# Driver.net
KiCad netlist of a schematic drawn in EAGLE
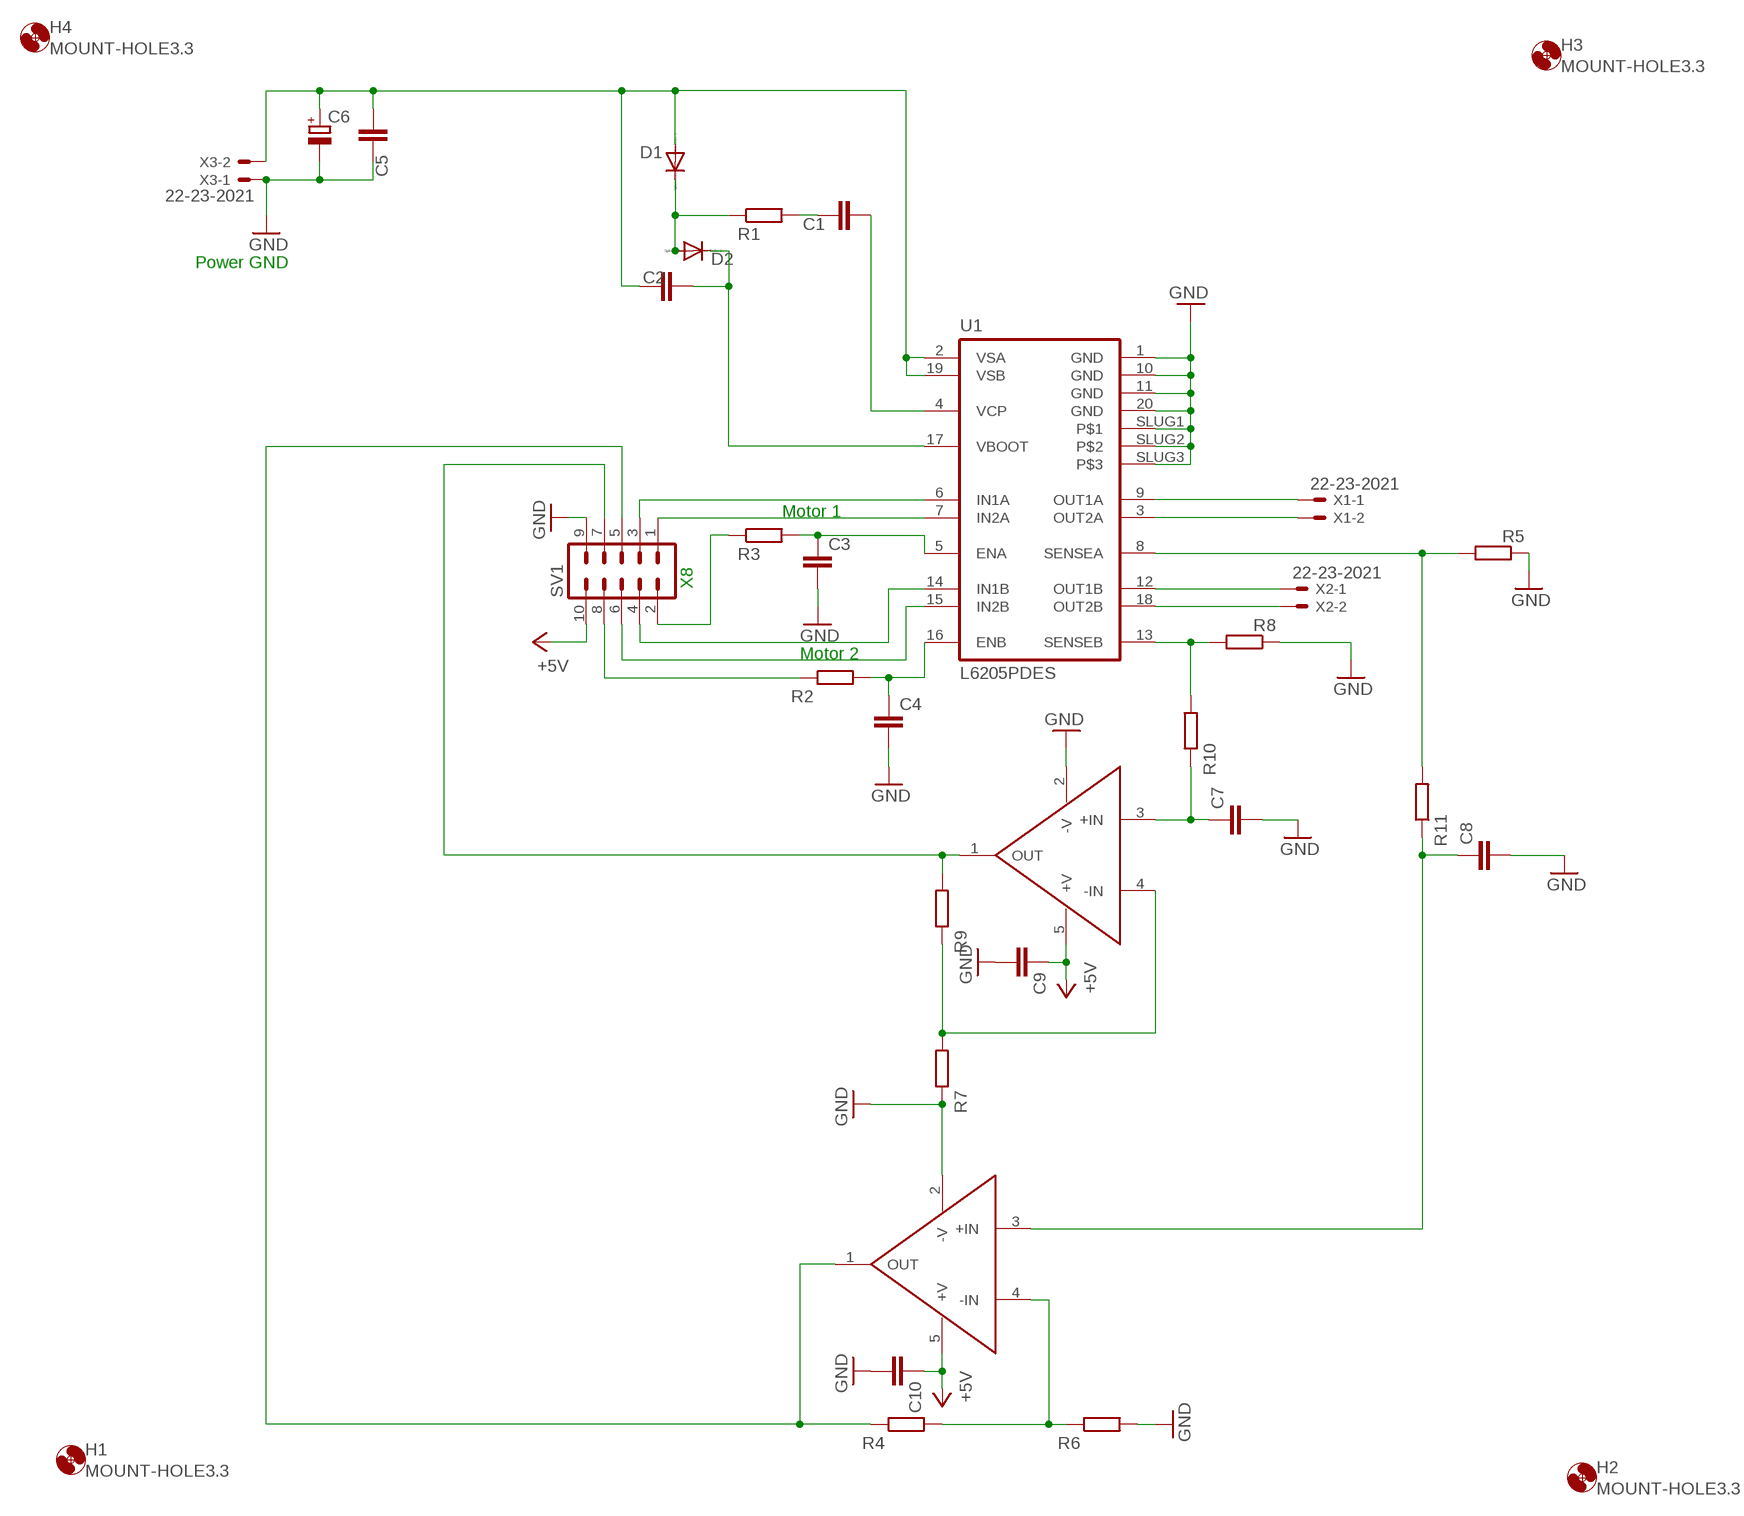
[diagram p0: schematic, sheet 1]

(export (version "E")
  (design (tool "Eeschema 10.0.6"))
  (components
    (comp (ref "C1")
      (value "C-EUC0805K")
      (footprint "eagle-import:C0805K")
      (libsource (lib "eagle-import") (part "C-EUC0805K"))
    )
    (comp (ref "C2")
      (value "C-EUC0805K")
      (footprint "eagle-import:C0805K")
      (libsource (lib "eagle-import") (part "C-EUC0805K"))
    )
    (comp (ref "C3")
      (value "C-EUC0805")
      (footprint "eagle-import:C0805")
      (libsource (lib "eagle-import") (part "C-EUC0805"))
    )
    (comp (ref "C4")
      (value "C-EUC0805")
      (footprint "eagle-import:C0805")
      (libsource (lib "eagle-import") (part "C-EUC0805"))
    )
    (comp (ref "C5")
      (value "C-EUC0805K")
      (footprint "eagle-import:C0805K")
      (libsource (lib "eagle-import") (part "C-EUC0805K"))
    )
    (comp (ref "C6")
      (value "CPOL-EUE")
      (footprint "eagle-import:PANASONIC_E")
      (libsource (lib "eagle-import") (part "CPOL-EUE"))
    )
    (comp (ref "C7")
      (value "C-EUC0805")
      (footprint "eagle-import:C0805")
      (libsource (lib "eagle-import") (part "C-EUC0805"))
    )
    (comp (ref "C8")
      (value "C-EUC0805")
      (footprint "eagle-import:C0805")
      (libsource (lib "eagle-import") (part "C-EUC0805"))
    )
    (comp (ref "C9")
      (value "C-EUC0805")
      (footprint "eagle-import:C0805")
      (libsource (lib "eagle-import") (part "C-EUC0805"))
    )
    (comp (ref "C10")
      (value "C-EUC0805")
      (footprint "eagle-import:C0805")
      (libsource (lib "eagle-import") (part "C-EUC0805"))
    )
    (comp (ref "D1")
      (value "DIODE-MINIMELF")
      (footprint "eagle-import:MINIMELF")
      (libsource (lib "eagle-import") (part "DIODE-MINIMELF"))
    )
    (comp (ref "D2")
      (value "DIODE-MINIMELF")
      (footprint "eagle-import:MINIMELF")
      (libsource (lib "eagle-import") (part "DIODE-MINIMELF"))
    )
    (comp (ref "H1")
      (value "MOUNT-HOLE3.3")
      (footprint "eagle-import:3,3")
      (libsource (lib "eagle-import") (part "MOUNT-HOLE3.3"))
    )
    (comp (ref "H2")
      (value "MOUNT-HOLE3.3")
      (footprint "eagle-import:3,3")
      (libsource (lib "eagle-import") (part "MOUNT-HOLE3.3"))
    )
    (comp (ref "H3")
      (value "MOUNT-HOLE3.3")
      (footprint "eagle-import:3,3")
      (libsource (lib "eagle-import") (part "MOUNT-HOLE3.3"))
    )
    (comp (ref "H4")
      (value "MOUNT-HOLE3.3")
      (footprint "eagle-import:3,3")
      (libsource (lib "eagle-import") (part "MOUNT-HOLE3.3"))
    )
    (comp (ref "R1")
      (value "R-EU_MELF0204W")
      (footprint "eagle-import:MINI_MELF-0204W")
      (libsource (lib "eagle-import") (part "R-EU_MELF0204W"))
    )
    (comp (ref "R2")
      (value "R-EU_MELF0204W")
      (footprint "eagle-import:MINI_MELF-0204W")
      (libsource (lib "eagle-import") (part "R-EU_MELF0204W"))
    )
    (comp (ref "R3")
      (value "R-EU_MELF0204W")
      (footprint "eagle-import:MINI_MELF-0204W")
      (libsource (lib "eagle-import") (part "R-EU_MELF0204W"))
    )
    (comp (ref "R4")
      (value "R-EU_MELF0204W")
      (footprint "eagle-import:MINI_MELF-0204W")
      (libsource (lib "eagle-import") (part "R-EU_MELF0204W"))
    )
    (comp (ref "R5")
      (value "R-EU_R2512W")
      (footprint "eagle-import:R2512W")
      (libsource (lib "eagle-import") (part "R-EU_R2512W"))
    )
    (comp (ref "R6")
      (value "R-EU_MELF0204W")
      (footprint "eagle-import:MINI_MELF-0204W")
      (libsource (lib "eagle-import") (part "R-EU_MELF0204W"))
    )
    (comp (ref "R7")
      (value "R-EU_MELF0204W")
      (footprint "eagle-import:MINI_MELF-0204W")
      (libsource (lib "eagle-import") (part "R-EU_MELF0204W"))
    )
    (comp (ref "R8")
      (value "R-EU_R2512W")
      (footprint "eagle-import:R2512W")
      (libsource (lib "eagle-import") (part "R-EU_R2512W"))
    )
    (comp (ref "R9")
      (value "R-EU_MELF0204W")
      (footprint "eagle-import:MINI_MELF-0204W")
      (libsource (lib "eagle-import") (part "R-EU_MELF0204W"))
    )
    (comp (ref "R10")
      (value "R-EU_MELF0204W")
      (footprint "eagle-import:MINI_MELF-0204W")
      (libsource (lib "eagle-import") (part "R-EU_MELF0204W"))
    )
    (comp (ref "R11")
      (value "R-EU_MELF0204W")
      (footprint "eagle-import:MINI_MELF-0204W")
      (libsource (lib "eagle-import") (part "R-EU_MELF0204W"))
    )
    (comp (ref "SV1")
      (value "ML10")
      (footprint "eagle-import:ML10")
      (libsource (lib "eagle-import") (part "ML10"))
    )
    (comp (ref "U$2")
      (value "LM7301")
      (footprint "eagle-import:SOT23-5")
      (libsource (lib "eagle-import") (part "LM7301"))
    )
    (comp (ref "U$3")
      (value "LM7301")
      (footprint "eagle-import:SOT23-5")
      (libsource (lib "eagle-import") (part "LM7301"))
    )
    (comp (ref "U1")
      (value "L6205PDES")
      (footprint "eagle-import:SO20POWER2")
      (libsource (lib "eagle-import") (part "L6205PDES"))
    )
    (comp (ref "X1")
      (value "22-23-2021")
      (footprint "eagle-import:22-23-2021")
      (fields (field (name "MF") "MOLEX"))
      (libsource (lib "eagle-import") (part "22-23-2021"))
    )
    (comp (ref "X2")
      (value "22-23-2021")
      (footprint "eagle-import:22-23-2021")
      (fields (field (name "MF") "MOLEX"))
      (libsource (lib "eagle-import") (part "22-23-2021"))
    )
    (comp (ref "X3")
      (value "22-23-2021")
      (footprint "eagle-import:22-23-2021")
      (fields (field (name "MF") "MOLEX"))
      (libsource (lib "eagle-import") (part "22-23-2021"))
    )
  )
  (nets
    (net (code "1") (name "+5V") (class "Default")
      (node (ref "C10") (pin "1") (pinfunction "1_1") (pintype "passive"))
      (node (ref "C9") (pin "1") (pinfunction "1_1") (pintype "passive"))
      (node (ref "SV1") (pin "10") (pinfunction "10_10") (pintype "passive"))
      (node (ref "U$2") (pin "5") (pinfunction "+V_5") (pintype "power_in"))
      (node (ref "U$3") (pin "5") (pinfunction "+V_5") (pintype "power_in"))
    )
    (net (code "2") (name "GND") (class "Default")
      (node (ref "C10") (pin "2") (pinfunction "2_2") (pintype "passive"))
      (node (ref "C3") (pin "2") (pinfunction "2_2") (pintype "passive"))
      (node (ref "C4") (pin "2") (pinfunction "2_2") (pintype "passive"))
      (node (ref "C5") (pin "1") (pinfunction "1_1") (pintype "passive"))
      (node (ref "C6") (pin "-") (pinfunction "-_-") (pintype "passive"))
      (node (ref "C7") (pin "2") (pinfunction "2_2") (pintype "passive"))
      (node (ref "C8") (pin "2") (pinfunction "2_2") (pintype "passive"))
      (node (ref "C9") (pin "2") (pinfunction "2_2") (pintype "passive"))
      (node (ref "R5") (pin "1") (pinfunction "1_1") (pintype "passive"))
      (node (ref "R6") (pin "2") (pinfunction "2_2") (pintype "passive"))
      (node (ref "R7") (pin "1") (pinfunction "1_1") (pintype "passive"))
      (node (ref "R8") (pin "1") (pinfunction "1_1") (pintype "passive"))
      (node (ref "SV1") (pin "9") (pinfunction "9_9") (pintype "passive"))
      (node (ref "U$2") (pin "2") (pinfunction "-V_2") (pintype "power_in"))
      (node (ref "U$3") (pin "2") (pinfunction "-V_2") (pintype "power_in"))
      (node (ref "U1") (pin "1") (pinfunction "GND_1") (pintype "power_in"))
      (node (ref "U1") (pin "10") (pinfunction "GND_10") (pintype "power_in"))
      (node (ref "U1") (pin "11") (pinfunction "GND_11") (pintype "power_in"))
      (node (ref "U1") (pin "20") (pinfunction "GND_20") (pintype "power_in"))
      (node (ref "U1") (pin "SLUG1") (pinfunction "P$1_SLUG1") (pintype "bidirectional"))
      (node (ref "U1") (pin "SLUG2") (pinfunction "P$2_SLUG2") (pintype "bidirectional"))
      (node (ref "U1") (pin "SLUG3") (pinfunction "P$3_SLUG3") (pintype "bidirectional"))
      (node (ref "X3") (pin "1") (pinfunction "S_1") (pintype "passive"))
    )
    (net (code "3") (name "Net-(C1-Pad1)") (class "Default")
      (node (ref "C1") (pin "1") (pinfunction "1_1") (pintype "passive"))
      (node (ref "R1") (pin "2") (pinfunction "2_2") (pintype "passive"))
    )
    (net (code "4") (name "Net-(D1-PadC)") (class "Default")
      (node (ref "D1") (pin "C") (pinfunction "C_C") (pintype "passive"))
      (node (ref "D2") (pin "A") (pinfunction "A_A") (pintype "passive"))
      (node (ref "R1") (pin "1") (pinfunction "1_1") (pintype "passive"))
    )
    (net (code "5") (name "Net-(R2-Pad1)") (class "Default")
      (node (ref "R2") (pin "1") (pinfunction "1_1") (pintype "passive"))
      (node (ref "SV1") (pin "8") (pinfunction "8_8") (pintype "passive"))
    )
    (net (code "6") (name "Net-(R3-Pad1)") (class "Default")
      (node (ref "R3") (pin "1") (pinfunction "1_1") (pintype "passive"))
      (node (ref "SV1") (pin "2") (pinfunction "2_2") (pintype "passive"))
    )
    (net (code "7") (name "Net-(U$2-+IN)") (class "Default")
      (node (ref "C8") (pin "1") (pinfunction "1_1") (pintype "passive"))
      (node (ref "R11") (pin "1") (pinfunction "1_1") (pintype "passive"))
      (node (ref "U$2") (pin "3") (pinfunction "+IN_3") (pintype "input"))
    )
    (net (code "8") (name "Net-(U$2--IN)") (class "Default")
      (node (ref "R4") (pin "2") (pinfunction "2_2") (pintype "passive"))
      (node (ref "R6") (pin "1") (pinfunction "1_1") (pintype "passive"))
      (node (ref "U$2") (pin "4") (pinfunction "-IN_4") (pintype "input"))
    )
    (net (code "9") (name "Net-(U$2-OUT)") (class "Default")
      (node (ref "R4") (pin "1") (pinfunction "1_1") (pintype "passive"))
      (node (ref "SV1") (pin "5") (pinfunction "5_5") (pintype "passive"))
      (node (ref "U$2") (pin "1") (pinfunction "OUT_1") (pintype "output"))
    )
    (net (code "10") (name "Net-(U$3-+IN)") (class "Default")
      (node (ref "C7") (pin "1") (pinfunction "1_1") (pintype "passive"))
      (node (ref "R10") (pin "1") (pinfunction "1_1") (pintype "passive"))
      (node (ref "U$3") (pin "3") (pinfunction "+IN_3") (pintype "input"))
    )
    (net (code "11") (name "Net-(U$3--IN)") (class "Default")
      (node (ref "R7") (pin "2") (pinfunction "2_2") (pintype "passive"))
      (node (ref "R9") (pin "1") (pinfunction "1_1") (pintype "passive"))
      (node (ref "U$3") (pin "4") (pinfunction "-IN_4") (pintype "input"))
    )
    (net (code "12") (name "Net-(U$3-OUT)") (class "Default")
      (node (ref "R9") (pin "2") (pinfunction "2_2") (pintype "passive"))
      (node (ref "SV1") (pin "7") (pinfunction "7_7") (pintype "passive"))
      (node (ref "U$3") (pin "1") (pinfunction "OUT_1") (pintype "output"))
    )
    (net (code "13") (name "Net-(U1-ENA)") (class "Default")
      (node (ref "C3") (pin "1") (pinfunction "1_1") (pintype "passive"))
      (node (ref "R3") (pin "2") (pinfunction "2_2") (pintype "passive"))
      (node (ref "U1") (pin "5") (pinfunction "ENA_5") (pintype "bidirectional"))
    )
    (net (code "14") (name "Net-(U1-ENB)") (class "Default")
      (node (ref "C4") (pin "1") (pinfunction "1_1") (pintype "passive"))
      (node (ref "R2") (pin "2") (pinfunction "2_2") (pintype "passive"))
      (node (ref "U1") (pin "16") (pinfunction "ENB_16") (pintype "bidirectional"))
    )
    (net (code "15") (name "Net-(U1-IN1A)") (class "Default")
      (node (ref "SV1") (pin "3") (pinfunction "3_3") (pintype "passive"))
      (node (ref "U1") (pin "6") (pinfunction "IN1A_6") (pintype "input"))
    )
    (net (code "16") (name "Net-(U1-IN1B)") (class "Default")
      (node (ref "SV1") (pin "4") (pinfunction "4_4") (pintype "passive"))
      (node (ref "U1") (pin "14") (pinfunction "IN1B_14") (pintype "input"))
    )
    (net (code "17") (name "Net-(U1-IN2A)") (class "Default")
      (node (ref "SV1") (pin "1") (pinfunction "1_1") (pintype "passive"))
      (node (ref "U1") (pin "7") (pinfunction "IN2A_7") (pintype "input"))
    )
    (net (code "18") (name "Net-(U1-IN2B)") (class "Default")
      (node (ref "SV1") (pin "6") (pinfunction "6_6") (pintype "passive"))
      (node (ref "U1") (pin "15") (pinfunction "IN2B_15") (pintype "input"))
    )
    (net (code "19") (name "Net-(U1-OUT1A)") (class "Default")
      (node (ref "U1") (pin "9") (pinfunction "OUT1A_9") (pintype "output"))
      (node (ref "X1") (pin "1") (pinfunction "S_1") (pintype "passive"))
    )
    (net (code "20") (name "Net-(U1-OUT1B)") (class "Default")
      (node (ref "U1") (pin "12") (pinfunction "OUT1B_12") (pintype "output"))
      (node (ref "X2") (pin "1") (pinfunction "S_1") (pintype "passive"))
    )
    (net (code "21") (name "Net-(U1-OUT2A)") (class "Default")
      (node (ref "U1") (pin "3") (pinfunction "OUT2A_3") (pintype "output"))
      (node (ref "X1") (pin "2") (pinfunction "S_2") (pintype "passive"))
    )
    (net (code "22") (name "Net-(U1-OUT2B)") (class "Default")
      (node (ref "U1") (pin "18") (pinfunction "OUT2B_18") (pintype "output"))
      (node (ref "X2") (pin "2") (pinfunction "S_2") (pintype "passive"))
    )
    (net (code "23") (name "Net-(U1-SENSEA)") (class "Default")
      (node (ref "R11") (pin "2") (pinfunction "2_2") (pintype "passive"))
      (node (ref "R5") (pin "2") (pinfunction "2_2") (pintype "passive"))
      (node (ref "U1") (pin "8") (pinfunction "SENSEA_8") (pintype "power_in"))
    )
    (net (code "24") (name "Net-(U1-SENSEB)") (class "Default")
      (node (ref "R10") (pin "2") (pinfunction "2_2") (pintype "passive"))
      (node (ref "R8") (pin "2") (pinfunction "2_2") (pintype "passive"))
      (node (ref "U1") (pin "13") (pinfunction "SENSEB_13") (pintype "power_in"))
    )
    (net (code "25") (name "Net-(U1-VBOOT)") (class "Default")
      (node (ref "C2") (pin "2") (pinfunction "2_2") (pintype "passive"))
      (node (ref "D2") (pin "C") (pinfunction "C_C") (pintype "passive"))
      (node (ref "U1") (pin "17") (pinfunction "VBOOT_17") (pintype "passive"))
    )
    (net (code "26") (name "Net-(U1-VCP)") (class "Default")
      (node (ref "C1") (pin "2") (pinfunction "2_2") (pintype "passive"))
      (node (ref "U1") (pin "4") (pinfunction "VCP_4") (pintype "passive"))
    )
    (net (code "27") (name "Net-(U1-VSA)") (class "Default")
      (node (ref "C2") (pin "1") (pinfunction "1_1") (pintype "passive"))
      (node (ref "C5") (pin "2") (pinfunction "2_2") (pintype "passive"))
      (node (ref "C6") (pin "+") (pinfunction "+_+") (pintype "passive"))
      (node (ref "D1") (pin "A") (pinfunction "A_A") (pintype "passive"))
      (node (ref "U1") (pin "19") (pinfunction "VSB_19") (pintype "power_in"))
      (node (ref "U1") (pin "2") (pinfunction "VSA_2") (pintype "power_in"))
      (node (ref "X3") (pin "2") (pinfunction "S_2") (pintype "passive"))
    )
  )
)
